# LC_-_Communication_Board.net
KiCad netlist of a schematic drawn in Altium Designer
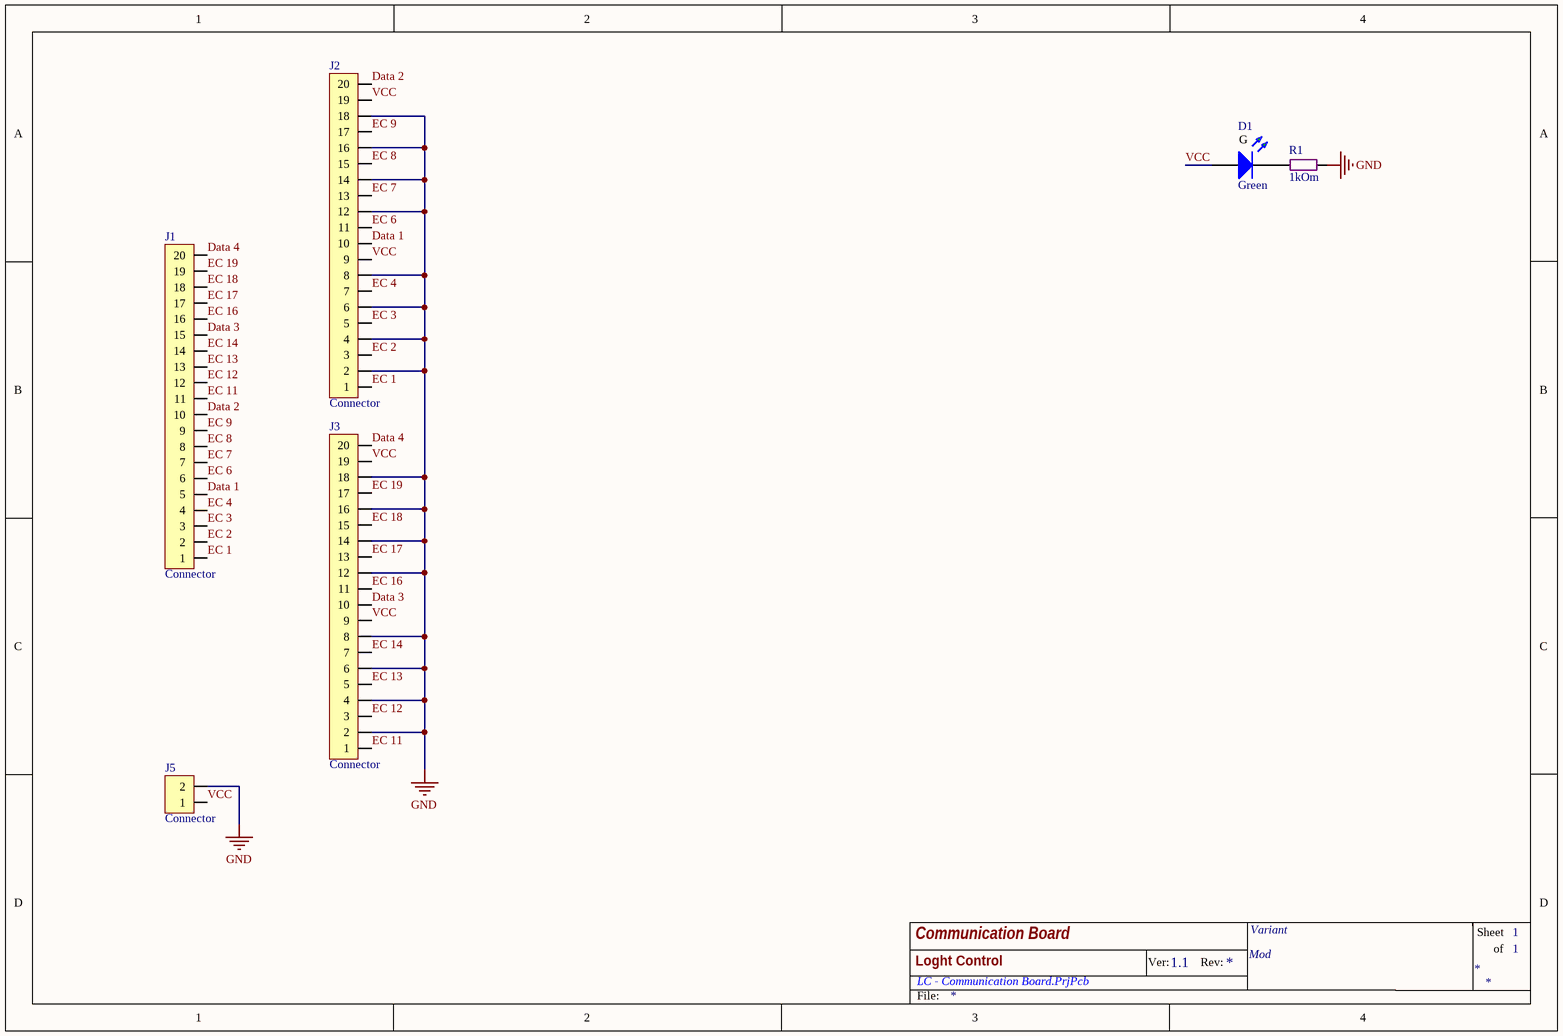
[diagram p0: LC - Communication Board.SchDoc]

(export (version "E")
  (design (tool "Eeschema 10.0.6"))
  (components
    (comp (ref "D1")
      (value "Green")
      (footprint "LED:LED SMD 0805 Green")
      (description "?2v ?20mA")
      (libsource (lib "LED") (part "Led SMD Green"))
    )
    (comp (ref "J1")
      (value "Connector")
      (footprint "Connector:LINE 2.54 x 20D (2 x 10) - BH")
      (description "Vert, Dbl line, Male")
      (libsource (lib "Connector") (part "PLD-20 (2 x 10)"))
    )
    (comp (ref "J2")
      (value "Connector")
      (footprint "Connector:LINE 2.54 x 20D (2 x 10) - BH")
      (description "Vert, Dbl line, Male")
      (libsource (lib "Connector") (part "PLD-20 (2 x 10)"))
    )
    (comp (ref "J3")
      (value "Connector")
      (footprint "Connector:LINE 2.54 x 20D (2 x 10) - BH")
      (description "Vert, Dbl line, Male")
      (libsource (lib "Connector") (part "PLD-20 (2 x 10)"))
    )
    (comp (ref "J5")
      (value "Connector")
      (footprint "Connector:DG301 5mm 2p")
      (description "DG301 series")
      (libsource (lib "Connector") (part "DG301-5.0-2P12"))
    )
    (comp (ref "R1")
      (value "1kOm")
      (footprint "PassiveComponents:SMD 0805 (2012)")
      (libsource (lib "PassiveComponents") (part "Res SMD 0805"))
    )
  )
  (nets
    (net (code "1") (name "/Data 1") (class "Default")
      (node (ref "J1") (pin "5") (pinfunction "5_5") (pintype "passive"))
      (node (ref "J2") (pin "10") (pinfunction "10_10") (pintype "passive"))
    )
    (net (code "2") (name "/Data 2") (class "Default")
      (node (ref "J1") (pin "10") (pinfunction "10_10") (pintype "passive"))
      (node (ref "J2") (pin "20") (pinfunction "20_20") (pintype "passive"))
    )
    (net (code "3") (name "/Data 3") (class "Default")
      (node (ref "J1") (pin "15") (pinfunction "15_15") (pintype "passive"))
      (node (ref "J3") (pin "10") (pinfunction "10_10") (pintype "passive"))
    )
    (net (code "4") (name "/Data 4") (class "Default")
      (node (ref "J1") (pin "20") (pinfunction "20_20") (pintype "passive"))
      (node (ref "J3") (pin "20") (pinfunction "20_20") (pintype "passive"))
    )
    (net (code "5") (name "/EC 1") (class "Default")
      (node (ref "J1") (pin "1") (pinfunction "1_1") (pintype "passive"))
      (node (ref "J2") (pin "1") (pinfunction "1_1") (pintype "passive"))
    )
    (net (code "6") (name "/EC 2") (class "Default")
      (node (ref "J1") (pin "2") (pinfunction "2_2") (pintype "passive"))
      (node (ref "J2") (pin "3") (pinfunction "3_3") (pintype "passive"))
    )
    (net (code "7") (name "/EC 3") (class "Default")
      (node (ref "J1") (pin "3") (pinfunction "3_3") (pintype "passive"))
      (node (ref "J2") (pin "5") (pinfunction "5_5") (pintype "passive"))
    )
    (net (code "8") (name "/EC 4") (class "Default")
      (node (ref "J1") (pin "4") (pinfunction "4_4") (pintype "passive"))
      (node (ref "J2") (pin "7") (pinfunction "7_7") (pintype "passive"))
    )
    (net (code "9") (name "/EC 6") (class "Default")
      (node (ref "J1") (pin "6") (pinfunction "6_6") (pintype "passive"))
      (node (ref "J2") (pin "11") (pinfunction "11_11") (pintype "passive"))
    )
    (net (code "10") (name "/EC 7") (class "Default")
      (node (ref "J1") (pin "7") (pinfunction "7_7") (pintype "passive"))
      (node (ref "J2") (pin "13") (pinfunction "13_13") (pintype "passive"))
    )
    (net (code "11") (name "/EC 8") (class "Default")
      (node (ref "J1") (pin "8") (pinfunction "8_8") (pintype "passive"))
      (node (ref "J2") (pin "15") (pinfunction "15_15") (pintype "passive"))
    )
    (net (code "12") (name "/EC 9") (class "Default")
      (node (ref "J1") (pin "9") (pinfunction "9_9") (pintype "passive"))
      (node (ref "J2") (pin "17") (pinfunction "17_17") (pintype "passive"))
    )
    (net (code "13") (name "/EC 11") (class "Default")
      (node (ref "J1") (pin "11") (pinfunction "11_11") (pintype "passive"))
      (node (ref "J3") (pin "1") (pinfunction "1_1") (pintype "passive"))
    )
    (net (code "14") (name "/EC 12") (class "Default")
      (node (ref "J1") (pin "12") (pinfunction "12_12") (pintype "passive"))
      (node (ref "J3") (pin "3") (pinfunction "3_3") (pintype "passive"))
    )
    (net (code "15") (name "/EC 13") (class "Default")
      (node (ref "J1") (pin "13") (pinfunction "13_13") (pintype "passive"))
      (node (ref "J3") (pin "5") (pinfunction "5_5") (pintype "passive"))
    )
    (net (code "16") (name "/EC 14") (class "Default")
      (node (ref "J1") (pin "14") (pinfunction "14_14") (pintype "passive"))
      (node (ref "J3") (pin "7") (pinfunction "7_7") (pintype "passive"))
    )
    (net (code "17") (name "/EC 16") (class "Default")
      (node (ref "J1") (pin "16") (pinfunction "16_16") (pintype "passive"))
      (node (ref "J3") (pin "11") (pinfunction "11_11") (pintype "passive"))
    )
    (net (code "18") (name "/EC 17") (class "Default")
      (node (ref "J1") (pin "17") (pinfunction "17_17") (pintype "passive"))
      (node (ref "J3") (pin "13") (pinfunction "13_13") (pintype "passive"))
    )
    (net (code "19") (name "/EC 18") (class "Default")
      (node (ref "J1") (pin "18") (pinfunction "18_18") (pintype "passive"))
      (node (ref "J3") (pin "15") (pinfunction "15_15") (pintype "passive"))
    )
    (net (code "20") (name "/EC 19") (class "Default")
      (node (ref "J1") (pin "19") (pinfunction "19_19") (pintype "passive"))
      (node (ref "J3") (pin "17") (pinfunction "17_17") (pintype "passive"))
    )
    (net (code "21") (name "/VCC") (class "Default")
      (node (ref "D1") (pin "A") (pinfunction "A_A") (pintype "passive"))
      (node (ref "J2") (pin "19") (pinfunction "19_19") (pintype "passive"))
      (node (ref "J2") (pin "9") (pinfunction "9_9") (pintype "passive"))
      (node (ref "J3") (pin "19") (pinfunction "19_19") (pintype "passive"))
      (node (ref "J3") (pin "9") (pinfunction "9_9") (pintype "passive"))
      (node (ref "J5") (pin "1") (pinfunction "1_1") (pintype "passive"))
    )
    (net (code "22") (name "GND") (class "Default")
      (node (ref "J2") (pin "12") (pinfunction "12_12") (pintype "passive"))
      (node (ref "J2") (pin "14") (pinfunction "14_14") (pintype "passive"))
      (node (ref "J2") (pin "16") (pinfunction "16_16") (pintype "passive"))
      (node (ref "J2") (pin "18") (pinfunction "18_18") (pintype "passive"))
      (node (ref "J2") (pin "2") (pinfunction "2_2") (pintype "passive"))
      (node (ref "J2") (pin "4") (pinfunction "4_4") (pintype "passive"))
      (node (ref "J2") (pin "6") (pinfunction "6_6") (pintype "passive"))
      (node (ref "J2") (pin "8") (pinfunction "8_8") (pintype "passive"))
      (node (ref "J3") (pin "12") (pinfunction "12_12") (pintype "passive"))
      (node (ref "J3") (pin "14") (pinfunction "14_14") (pintype "passive"))
      (node (ref "J3") (pin "16") (pinfunction "16_16") (pintype "passive"))
      (node (ref "J3") (pin "18") (pinfunction "18_18") (pintype "passive"))
      (node (ref "J3") (pin "2") (pinfunction "2_2") (pintype "passive"))
      (node (ref "J3") (pin "4") (pinfunction "4_4") (pintype "passive"))
      (node (ref "J3") (pin "6") (pinfunction "6_6") (pintype "passive"))
      (node (ref "J3") (pin "8") (pinfunction "8_8") (pintype "passive"))
      (node (ref "J5") (pin "2") (pinfunction "2_2") (pintype "passive"))
      (node (ref "R1") (pin "2") (pinfunction "2_2") (pintype "passive"))
    )
    (net (code "23") (name "Net-(D1-PadK)") (class "Default")
      (node (ref "D1") (pin "K") (pinfunction "K_K") (pintype "passive"))
      (node (ref "R1") (pin "1") (pinfunction "1_1") (pintype "passive"))
    )
  )
)
